# Microcontroller.net
KiCad netlist of a schematic drawn in Altium Designer
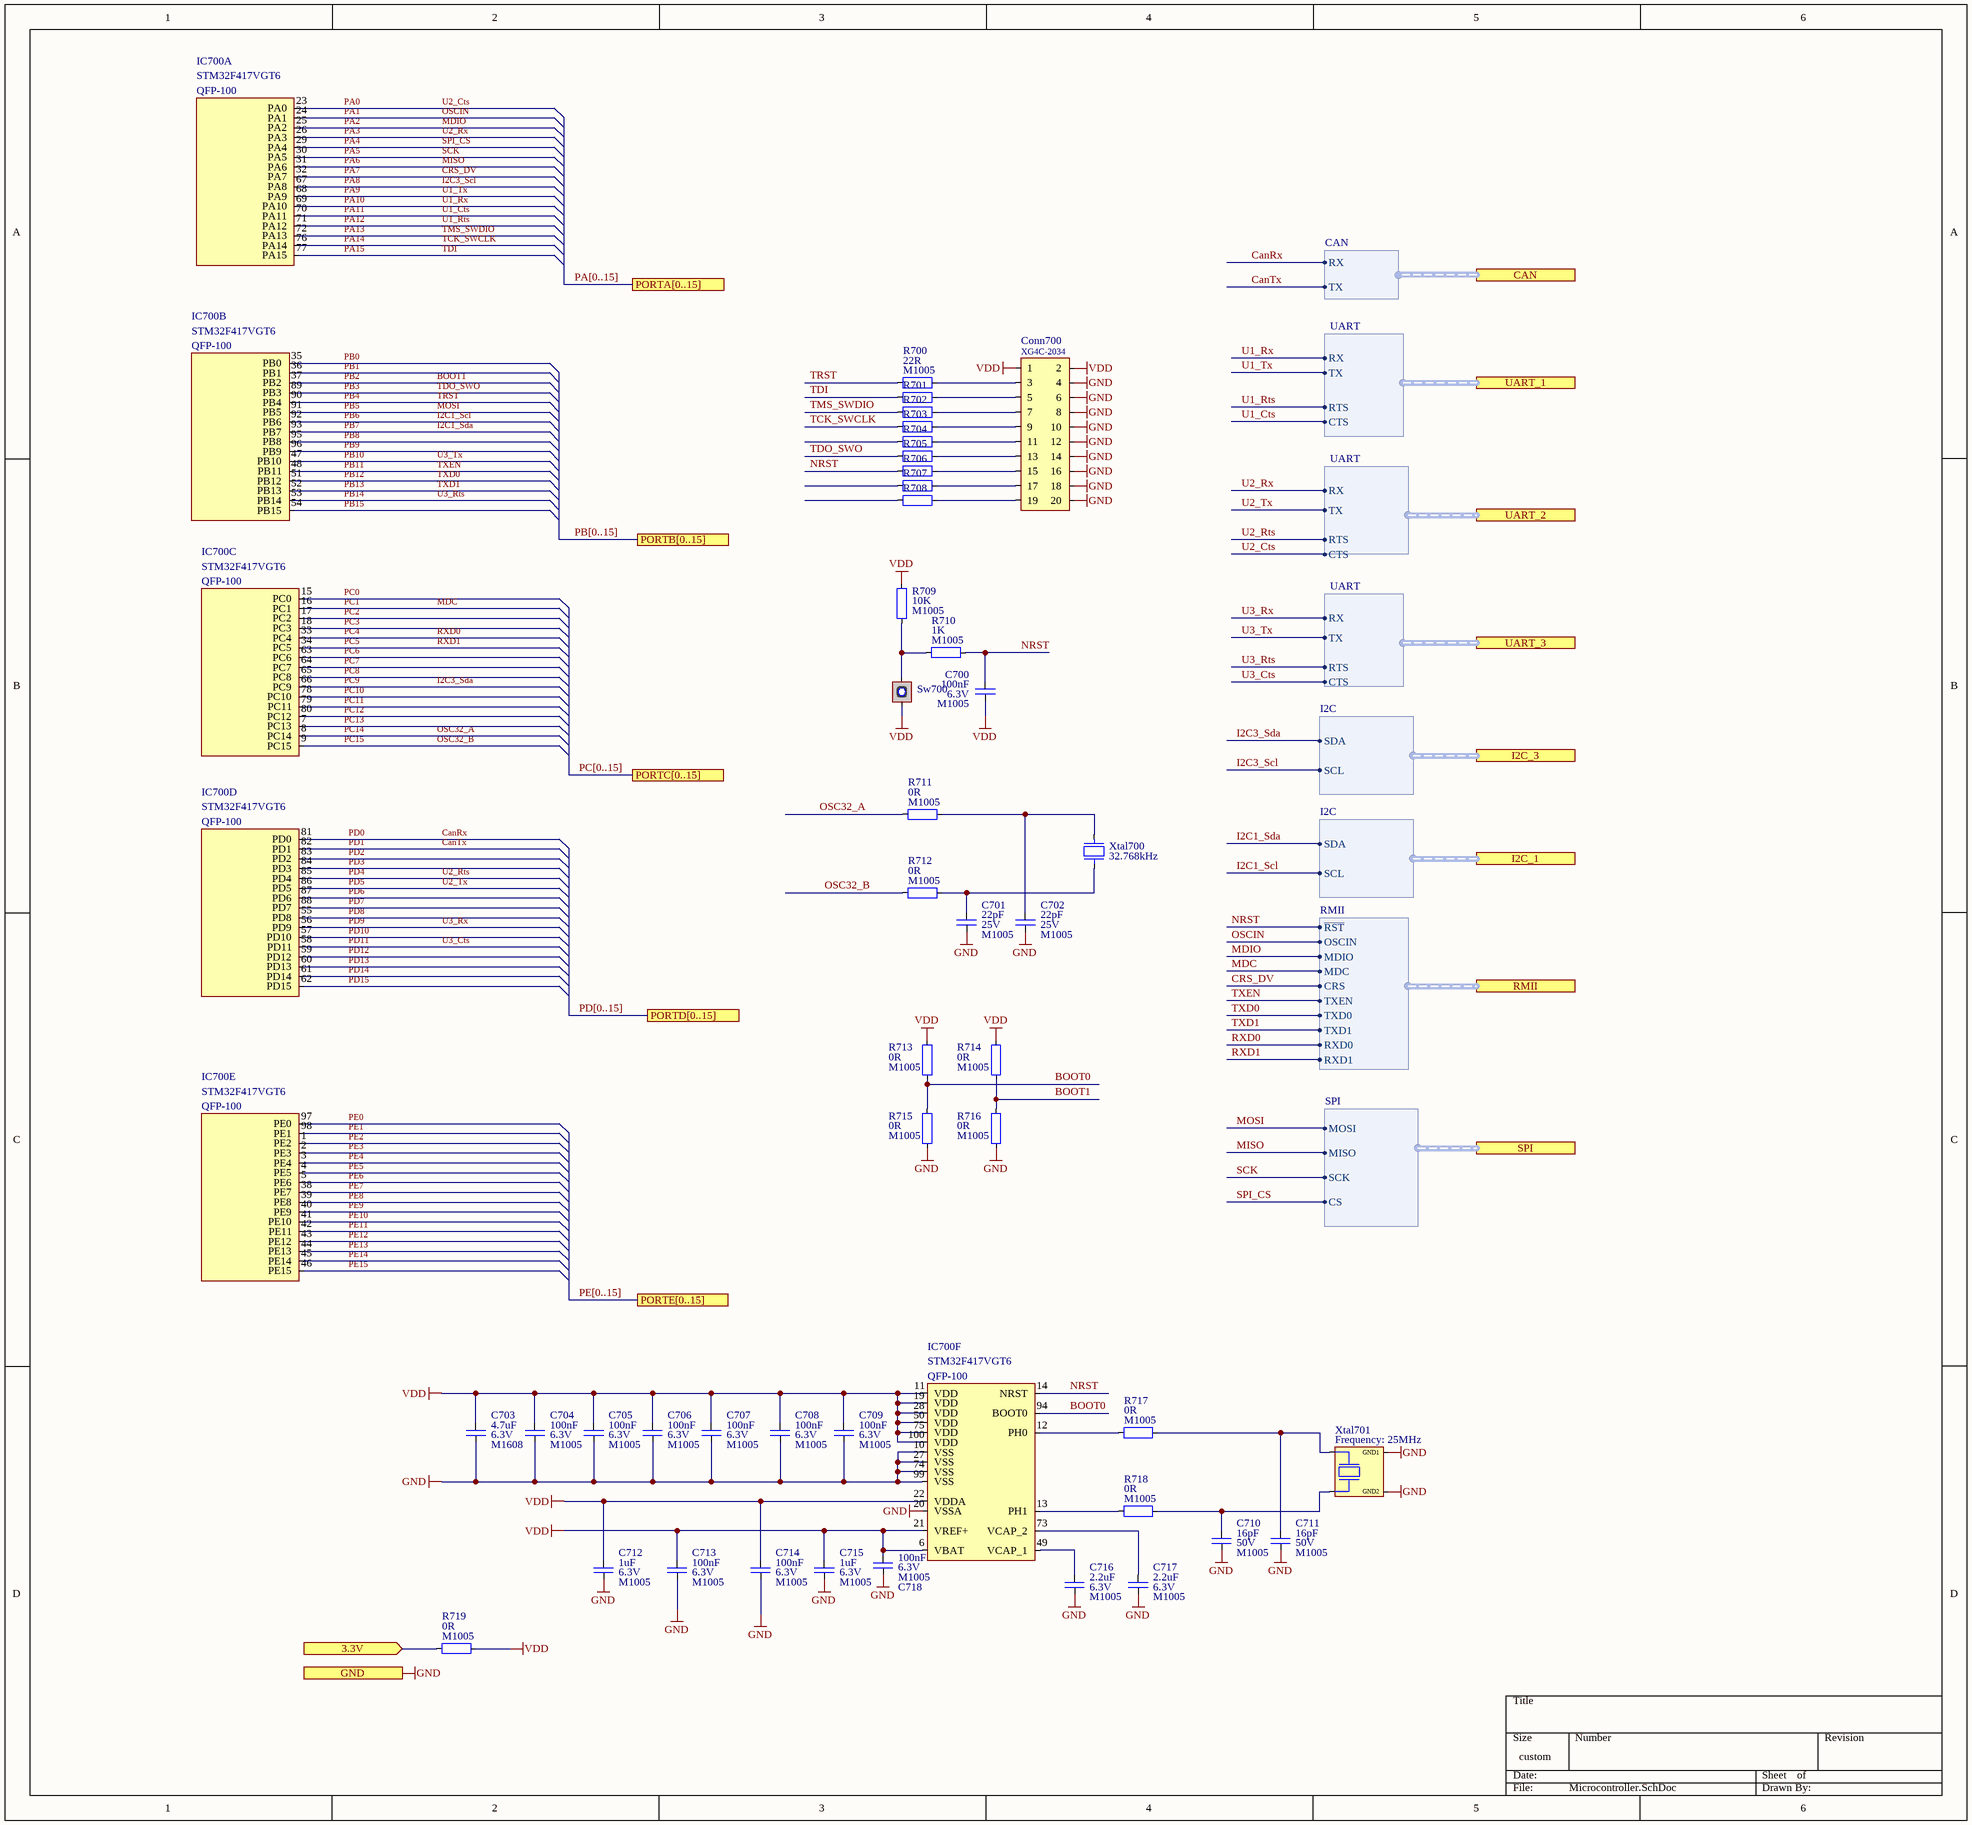
[diagram p0: Microcontroller.SchDoc]

(export (version "E")
  (design (tool "Eeschema 10.0.6"))
  (components
    (comp (ref "C700")
      (value "100nF")
      (footprint "Capacitor_Ceramic_M1005_I0402")
      (description "Cap, Cer, 100nF, 6.3V, M1005")
      (fields
        (field (name "VOLTAGE") "6.3V")
        (field (name "MANUFACTURER PART NUMBER") "04026D104KAT4A")
        (field (name "MANUFACTURER") "Kyocera")
        (field (name "PACKAGE") "M1005")
      )
      (libsource (lib "Capacitor") (part "Capacitor_Ceramic"))
    )
    (comp (ref "C701")
      (value "22pF")
      (footprint "Capacitor_Ceramic_M1005_I0402")
      (description "Cap, Cer, 22pF, 25V, M1005")
      (fields
        (field (name "VOLTAGE") "25V")
        (field (name "MANUFACTURER PART NUMBER") "0402N220J250CT")
        (field (name "MANUFACTURER") "Walsin")
        (field (name "PACKAGE") "M1005")
      )
      (libsource (lib "Capacitor") (part "Capacitor_Ceramic"))
    )
    (comp (ref "C702")
      (value "22pF")
      (footprint "Capacitor_Ceramic_M1005_I0402")
      (description "Cap, Cer, 22pF, 25V, M1005")
      (fields
        (field (name "VOLTAGE") "25V")
        (field (name "MANUFACTURER PART NUMBER") "0402N220J250CT")
        (field (name "MANUFACTURER") "Walsin")
        (field (name "PACKAGE") "M1005")
      )
      (libsource (lib "Capacitor") (part "Capacitor_Ceramic"))
    )
    (comp (ref "C703")
      (value "4.7uF")
      (footprint "Capacitor_Ceramic_M1608_I0603")
      (description "Cap, Cer, 4.7uF, 6.3V, M1608")
      (fields
        (field (name "VOLTAGE") "6.3V")
        (field (name "MANUFACTURER PART NUMBER") "CL10A475KQ8NNNC")
        (field (name "MANUFACTURER") "Samsung")
        (field (name "PACKAGE") "M1608")
      )
      (libsource (lib "Capacitor") (part "Capacitor_Ceramic"))
    )
    (comp (ref "C704")
      (value "100nF")
      (footprint "Capacitor_Ceramic_M1005_I0402")
      (description "Cap, Cer, 100nF, 6.3V, M1005")
      (fields
        (field (name "VOLTAGE") "6.3V")
        (field (name "MANUFACTURER PART NUMBER") "04026D104KAT4A")
        (field (name "MANUFACTURER") "Kyocera")
        (field (name "PACKAGE") "M1005")
      )
      (libsource (lib "Capacitor") (part "Capacitor_Ceramic"))
    )
    (comp (ref "C705")
      (value "100nF")
      (footprint "Capacitor_Ceramic_M1005_I0402")
      (description "Cap, Cer, 100nF, 6.3V, M1005")
      (fields
        (field (name "VOLTAGE") "6.3V")
        (field (name "MANUFACTURER PART NUMBER") "04026D104KAT4A")
        (field (name "MANUFACTURER") "Kyocera")
        (field (name "PACKAGE") "M1005")
      )
      (libsource (lib "Capacitor") (part "Capacitor_Ceramic"))
    )
    (comp (ref "C706")
      (value "100nF")
      (footprint "Capacitor_Ceramic_M1005_I0402")
      (description "Cap, Cer, 100nF, 6.3V, M1005")
      (fields
        (field (name "VOLTAGE") "6.3V")
        (field (name "MANUFACTURER PART NUMBER") "04026D104KAT4A")
        (field (name "MANUFACTURER") "Kyocera")
        (field (name "PACKAGE") "M1005")
      )
      (libsource (lib "Capacitor") (part "Capacitor_Ceramic"))
    )
    (comp (ref "C707")
      (value "100nF")
      (footprint "Capacitor_Ceramic_M1005_I0402")
      (description "Cap, Cer, 100nF, 6.3V, M1005")
      (fields
        (field (name "VOLTAGE") "6.3V")
        (field (name "MANUFACTURER PART NUMBER") "04026D104KAT4A")
        (field (name "MANUFACTURER") "Kyocera")
        (field (name "PACKAGE") "M1005")
      )
      (libsource (lib "Capacitor") (part "Capacitor_Ceramic"))
    )
    (comp (ref "C708")
      (value "100nF")
      (footprint "Capacitor_Ceramic_M1005_I0402")
      (description "Cap, Cer, 100nF, 6.3V, M1005")
      (fields
        (field (name "VOLTAGE") "6.3V")
        (field (name "MANUFACTURER PART NUMBER") "04026D104KAT4A")
        (field (name "MANUFACTURER") "Kyocera")
        (field (name "PACKAGE") "M1005")
      )
      (libsource (lib "Capacitor") (part "Capacitor_Ceramic"))
    )
    (comp (ref "C709")
      (value "100nF")
      (footprint "Capacitor_Ceramic_M1005_I0402")
      (description "Cap, Cer, 100nF, 6.3V, M1005")
      (fields
        (field (name "VOLTAGE") "6.3V")
        (field (name "MANUFACTURER PART NUMBER") "04026D104KAT4A")
        (field (name "MANUFACTURER") "Kyocera")
        (field (name "PACKAGE") "M1005")
      )
      (libsource (lib "Capacitor") (part "Capacitor_Ceramic"))
    )
    (comp (ref "C710")
      (value "16pF")
      (footprint "Capacitor_Ceramic_M1005_I0402")
      (description "Cap, Cer, 16pF, 50V, M1005")
      (fields
        (field (name "VOLTAGE") "50V")
        (field (name "MANUFACTURER PART NUMBER") "0402N160J500CT")
        (field (name "MANUFACTURER") "Walsin")
        (field (name "PACKAGE") "M1005")
      )
      (libsource (lib "Capacitor") (part "Capacitor_Ceramic"))
    )
    (comp (ref "C711")
      (value "16pF")
      (footprint "Capacitor_Ceramic_M1005_I0402")
      (description "Cap, Cer, 16pF, 50V, M1005")
      (fields
        (field (name "VOLTAGE") "50V")
        (field (name "MANUFACTURER PART NUMBER") "0402N160J500CT")
        (field (name "MANUFACTURER") "Walsin")
        (field (name "PACKAGE") "M1005")
      )
      (libsource (lib "Capacitor") (part "Capacitor_Ceramic"))
    )
    (comp (ref "C712")
      (value "1uF")
      (footprint "Capacitor_Ceramic_M1005_I0402")
      (description "Cap, Cer, 1uF, 6.3V, M1005")
      (fields
        (field (name "VOLTAGE") "6.3V")
        (field (name "MANUFACTURER PART NUMBER") "CL05A105MQ5NNNC")
        (field (name "MANUFACTURER") "Samsung")
        (field (name "PACKAGE") "M1005")
      )
      (libsource (lib "Capacitor") (part "Capacitor_Ceramic"))
    )
    (comp (ref "C713")
      (value "100nF")
      (footprint "Capacitor_Ceramic_M1005_I0402")
      (description "Cap, Cer, 100nF, 6.3V, M1005")
      (fields
        (field (name "VOLTAGE") "6.3V")
        (field (name "MANUFACTURER PART NUMBER") "04026D104KAT4A")
        (field (name "MANUFACTURER") "Kyocera")
        (field (name "PACKAGE") "M1005")
      )
      (libsource (lib "Capacitor") (part "Capacitor_Ceramic"))
    )
    (comp (ref "C714")
      (value "100nF")
      (footprint "Capacitor_Ceramic_M1005_I0402")
      (description "Cap, Cer, 100nF, 6.3V, M1005")
      (fields
        (field (name "VOLTAGE") "6.3V")
        (field (name "MANUFACTURER PART NUMBER") "04026D104KAT4A")
        (field (name "MANUFACTURER") "Kyocera")
        (field (name "PACKAGE") "M1005")
      )
      (libsource (lib "Capacitor") (part "Capacitor_Ceramic"))
    )
    (comp (ref "C715")
      (value "1uF")
      (footprint "Capacitor_Ceramic_M1005_I0402")
      (description "Cap, Cer, 1uF, 6.3V, M1005")
      (fields
        (field (name "VOLTAGE") "6.3V")
        (field (name "MANUFACTURER PART NUMBER") "CL05A105MQ5NNNC")
        (field (name "MANUFACTURER") "Samsung")
        (field (name "PACKAGE") "M1005")
      )
      (libsource (lib "Capacitor") (part "Capacitor_Ceramic"))
    )
    (comp (ref "C716")
      (value "2.2uF")
      (footprint "Capacitor_Ceramic_M1005_I0402")
      (description "Cap, Cer, 2.2uF, 6.3V, M1005")
      (fields
        (field (name "VOLTAGE") "6.3V")
        (field (name "MANUFACTURER PART NUMBER") "CL05A225MQ5NNNC")
        (field (name "MANUFACTURER") "Samsung")
        (field (name "PACKAGE") "M1005")
      )
      (libsource (lib "Capacitor") (part "Capacitor_Ceramic"))
    )
    (comp (ref "C717")
      (value "2.2uF")
      (footprint "Capacitor_Ceramic_M1005_I0402")
      (description "Cap, Cer, 2.2uF, 6.3V, M1005")
      (fields
        (field (name "VOLTAGE") "6.3V")
        (field (name "MANUFACTURER PART NUMBER") "CL05A225MQ5NNNC")
        (field (name "MANUFACTURER") "Samsung")
        (field (name "PACKAGE") "M1005")
      )
      (libsource (lib "Capacitor") (part "Capacitor_Ceramic"))
    )
    (comp (ref "C718")
      (value "100nF")
      (footprint "Capacitor_Ceramic_M1005_I0402")
      (description "Cap, Cer, 100nF, 6.3V, M1005")
      (fields
        (field (name "VOLTAGE") "6.3V")
        (field (name "MANUFACTURER PART NUMBER") "04026D104KAT4A")
        (field (name "MANUFACTURER") "Kyocera")
        (field (name "PACKAGE") "M1005")
      )
      (libsource (lib "Capacitor") (part "Capacitor_Ceramic"))
    )
    (comp (ref "Conn700")
      (value "Connector - 20P")
      (footprint "Connector - Omron, XG4C-2034")
      (description "Conn, Header, 20P, RA, TH, Shrouded")
      (fields (field (name "MANUFACTURER") "Omron") (field (name "MANUFACTURER PART NUMBER") "XG4C-2034"))
      (libsource (lib "Connector - Header") (part "Connector - 20P"))
    )
    (comp (ref "IC700")
      (value "STM, STM32F417VxTx")
      (footprint "QFP-100, 14mm x 14mm, 0.5mm")
      (description "IC, MCU, STM32F417, QFP-100")
      (fields
        (field (name "MANUFACTURER") "STM")
        (field (name "MANUFACTURER PART NUMBER") "STM32F417VGT6")
        (field (name "PACKAGE") "QFP-100")
      )
      (libsource (lib "IC - MCU") (part "STM, STM32F417VxTx"))
    )
    (comp (ref "R700")
      (value "22R")
      (footprint "Resistor_Smd_M1005_I0402")
      (description "Res, 22R, 1%, M1005")
      (fields
        (field (name "TOLERANCE") "1%")
        (field (name "MANUFACTURER") "Yageo")
        (field (name "PACKAGE") "M1005")
      )
      (libsource (lib "Resistor") (part "Resistor"))
    )
    (comp (ref "R701")
      (value "Resistor")
      (footprint "Resistor_Smd_M1005_I0402")
      (description "Res, 22R, 1%, M1005")
      (fields (field (name "TOLERANCE") "1%") (field (name "MANUFACTURER") "Yageo"))
      (libsource (lib "Resistor") (part "Resistor"))
    )
    (comp (ref "R702")
      (value "Resistor")
      (footprint "Resistor_Smd_M1005_I0402")
      (description "Res, 22R, 1%, M1005")
      (fields (field (name "TOLERANCE") "1%") (field (name "MANUFACTURER") "Yageo"))
      (libsource (lib "Resistor") (part "Resistor"))
    )
    (comp (ref "R703")
      (value "Resistor")
      (footprint "Resistor_Smd_M1005_I0402")
      (description "Res, 22R, 1%, M1005")
      (fields (field (name "TOLERANCE") "1%") (field (name "MANUFACTURER") "Yageo"))
      (libsource (lib "Resistor") (part "Resistor"))
    )
    (comp (ref "R704")
      (value "Resistor")
      (footprint "Resistor_Smd_M1005_I0402")
      (description "Res, 22R, 1%, M1005")
      (fields (field (name "TOLERANCE") "1%") (field (name "MANUFACTURER") "Yageo"))
      (libsource (lib "Resistor") (part "Resistor"))
    )
    (comp (ref "R705")
      (value "Resistor")
      (footprint "Resistor_Smd_M1005_I0402")
      (description "Res, 22R, 1%, M1005")
      (fields (field (name "TOLERANCE") "1%") (field (name "MANUFACTURER") "Yageo"))
      (libsource (lib "Resistor") (part "Resistor"))
    )
    (comp (ref "R706")
      (value "Resistor")
      (footprint "Resistor_Smd_M1005_I0402")
      (description "Res, 22R, 1%, M1005")
      (fields (field (name "TOLERANCE") "1%") (field (name "MANUFACTURER") "Yageo"))
      (libsource (lib "Resistor") (part "Resistor"))
    )
    (comp (ref "R707")
      (value "Resistor")
      (footprint "Resistor_Smd_M1005_I0402")
      (description "Res, 22R, 1%, M1005")
      (fields (field (name "TOLERANCE") "1%") (field (name "MANUFACTURER") "Yageo"))
      (libsource (lib "Resistor") (part "Resistor"))
    )
    (comp (ref "R708")
      (value "Resistor")
      (footprint "Resistor_Smd_M1005_I0402")
      (description "Res, 22R, 1%, M1005")
      (fields (field (name "TOLERANCE") "1%") (field (name "MANUFACTURER") "Yageo"))
      (libsource (lib "Resistor") (part "Resistor"))
    )
    (comp (ref "R709")
      (value "10K")
      (footprint "Resistor_Smd_M1005_I0402")
      (description "Res, 10K, 1%, M1005")
      (fields
        (field (name "TOLERANCE") "1%")
        (field (name "MANUFACTURER") "Yageo")
        (field (name "PACKAGE") "M1005")
      )
      (libsource (lib "Resistor") (part "Resistor"))
    )
    (comp (ref "R710")
      (value "1K")
      (footprint "Resistor_Smd_M1005_I0402")
      (description "Res, 1K, 1%, M1005")
      (fields
        (field (name "TOLERANCE") "1%")
        (field (name "MANUFACTURER") "Yageo")
        (field (name "PACKAGE") "M1005")
      )
      (libsource (lib "Resistor") (part "Resistor"))
    )
    (comp (ref "R711")
      (value "0R")
      (footprint "Resistor_Smd_M1005_I0402")
      (description "Res, 0R, M1005")
      (fields
        (field (name "MANUFACTURER") "Yageo")
        (field (name "MANUFACTURER PART NUMBER") "RC0402FR-070RL")
        (field (name "PACKAGE") "M1005")
      )
      (libsource (lib "Resistor") (part "Resistor"))
    )
    (comp (ref "R712")
      (value "0R")
      (footprint "Resistor_Smd_M1005_I0402")
      (description "Res, 0R, M1005")
      (fields
        (field (name "MANUFACTURER") "Yageo")
        (field (name "MANUFACTURER PART NUMBER") "RC0402FR-070RL")
        (field (name "PACKAGE") "M1005")
      )
      (libsource (lib "Resistor") (part "Resistor"))
    )
    (comp (ref "R713")
      (value "0R")
      (footprint "Resistor_Smd_M1005_I0402")
      (description "Res, 0R, M1005")
      (fields
        (field (name "MANUFACTURER") "Yageo")
        (field (name "MANUFACTURER PART NUMBER") "RC0402FR-070RL")
        (field (name "PACKAGE") "M1005")
      )
      (libsource (lib "Resistor") (part "Resistor"))
    )
    (comp (ref "R714")
      (value "0R")
      (footprint "Resistor_Smd_M1005_I0402")
      (description "Res, 0R, M1005")
      (fields
        (field (name "MANUFACTURER") "Yageo")
        (field (name "MANUFACTURER PART NUMBER") "RC0402FR-070RL")
        (field (name "PACKAGE") "M1005")
      )
      (libsource (lib "Resistor") (part "Resistor"))
    )
    (comp (ref "R715")
      (value "0R")
      (footprint "Resistor_Smd_M1005_I0402")
      (description "Res, 0R, M1005")
      (fields
        (field (name "MANUFACTURER") "Yageo")
        (field (name "MANUFACTURER PART NUMBER") "RC0402FR-070RL")
        (field (name "PACKAGE") "M1005")
      )
      (libsource (lib "Resistor") (part "Resistor"))
    )
    (comp (ref "R716")
      (value "0R")
      (footprint "Resistor_Smd_M1005_I0402")
      (description "Res, 0R, M1005")
      (fields
        (field (name "MANUFACTURER") "Yageo")
        (field (name "MANUFACTURER PART NUMBER") "RC0402FR-070RL")
        (field (name "PACKAGE") "M1005")
      )
      (libsource (lib "Resistor") (part "Resistor"))
    )
    (comp (ref "R717")
      (value "0R")
      (footprint "Resistor_Smd_M1005_I0402")
      (description "Res, 0R, M1005")
      (fields
        (field (name "MANUFACTURER") "Yageo")
        (field (name "MANUFACTURER PART NUMBER") "RC0402FR-070RL")
        (field (name "PACKAGE") "M1005")
      )
      (libsource (lib "Resistor") (part "Resistor"))
    )
    (comp (ref "R718")
      (value "0R")
      (footprint "Resistor_Smd_M1005_I0402")
      (description "Res, 0R, M1005")
      (fields
        (field (name "MANUFACTURER") "Yageo")
        (field (name "MANUFACTURER PART NUMBER") "RC0402FR-070RL")
        (field (name "PACKAGE") "M1005")
      )
      (libsource (lib "Resistor") (part "Resistor"))
    )
    (comp (ref "R719")
      (value "0R")
      (footprint "Resistor_Smd_M1005_I0402")
      (description "Res, 0R, M1005")
      (fields
        (field (name "MANUFACTURER") "Yageo")
        (field (name "MANUFACTURER PART NUMBER") "RC0402FR-070RL")
        (field (name "PACKAGE") "M1005")
      )
      (libsource (lib "Resistor") (part "Resistor"))
    )
    (comp (ref "Sw700")
      (value "Tactile, SPST")
      (footprint "Tactile, SPST - Panasonic, EVQQ2")
      (libsource (lib "Switch") (part "Tactile, SPST"))
    )
    (comp (ref "Xtal700")
      (value "Crystal")
      (footprint "NDK, NX3215SA")
      (description "XTAL, 32.768kHz, 12.5pF")
      (fields
        (field (name "MANUFACTURER") "NDK")
        (field (name "FREQUENCY") "32.768kHz")
        (field (name "MANUFACTURER PART NUMBER") "NX3215SA-32.768K-STD-MUS-2")
      )
      (libsource (lib "Crystal") (part "Crystal"))
    )
    (comp (ref "Xtal701")
      (value "Crystal, Two Gnd Pins")
      (footprint "Kyocera, CX3225SB")
      (description "XTAL, 25MHz, 12pF")
      (fields
        (field (name "MANUFACTURER") "Kyocera")
        (field (name "FREQUENCY") "25MHz")
        (field (name "MANUFACTURER PART NUMBER") "CX3225SB25000H0FLJCC")
      )
      (libsource (lib "Crystal") (part "Crystal, Two Gnd Pins"))
    )
  )
  (nets
    (net (code "6") (name "/3.3V") (class "Default")
      (node (ref "R719") (pin "1") (pinfunction "1_1") (pintype "passive"))
    )
    (net (code "7") (name "/BOOT0") (class "Default")
      (node (ref "IC700") (pin "94") (pinfunction "BOOT0_94") (pintype "passive"))
      (node (ref "R713") (pin "1") (pinfunction "1_1") (pintype "passive"))
      (node (ref "R715") (pin "2") (pinfunction "2_2") (pintype "passive"))
    )
    (net (code "8") (name "/NRST") (class "Default")
      (node (ref "C700") (pin "1") (pinfunction "1_1") (pintype "passive"))
      (node (ref "IC700") (pin "14") (pinfunction "NRST_14") (pintype "passive"))
      (node (ref "R706") (pin "1") (pinfunction "1_1") (pintype "passive"))
      (node (ref "R710") (pin "2") (pinfunction "2_2") (pintype "passive"))
    )
    (net (code "9") (name "/PA0") (class "Default")
      (node (ref "IC700") (pin "23") (pinfunction "PA0_23") (pintype "passive"))
    )
    (net (code "10") (name "/PA1") (class "Default")
      (node (ref "IC700") (pin "24") (pinfunction "PA1_24") (pintype "passive"))
    )
    (net (code "11") (name "/PA2") (class "Default")
      (node (ref "IC700") (pin "25") (pinfunction "PA2_25") (pintype "passive"))
    )
    (net (code "12") (name "/PA3") (class "Default")
      (node (ref "IC700") (pin "26") (pinfunction "PA3_26") (pintype "passive"))
    )
    (net (code "13") (name "/PA4") (class "Default")
      (node (ref "IC700") (pin "29") (pinfunction "PA4_29") (pintype "passive"))
    )
    (net (code "14") (name "/PA5") (class "Default")
      (node (ref "IC700") (pin "30") (pinfunction "PA5_30") (pintype "passive"))
    )
    (net (code "15") (name "/PA6") (class "Default")
      (node (ref "IC700") (pin "31") (pinfunction "PA6_31") (pintype "passive"))
    )
    (net (code "16") (name "/PA7") (class "Default")
      (node (ref "IC700") (pin "32") (pinfunction "PA7_32") (pintype "passive"))
    )
    (net (code "17") (name "/PA8") (class "Default")
      (node (ref "IC700") (pin "67") (pinfunction "PA8_67") (pintype "passive"))
    )
    (net (code "18") (name "/PA9") (class "Default")
      (node (ref "IC700") (pin "68") (pinfunction "PA9_68") (pintype "passive"))
    )
    (net (code "19") (name "/PA10") (class "Default")
      (node (ref "IC700") (pin "69") (pinfunction "PA10_69") (pintype "passive"))
    )
    (net (code "20") (name "/PA11") (class "Default")
      (node (ref "IC700") (pin "70") (pinfunction "PA11_70") (pintype "passive"))
    )
    (net (code "21") (name "/PA12") (class "Default")
      (node (ref "IC700") (pin "71") (pinfunction "PA12_71") (pintype "passive"))
    )
    (net (code "22") (name "/PA13") (class "Default")
      (node (ref "IC700") (pin "72") (pinfunction "PA13_72") (pintype "passive"))
      (node (ref "R702") (pin "1") (pinfunction "1_1") (pintype "passive"))
    )
    (net (code "23") (name "/PA14") (class "Default")
      (node (ref "IC700") (pin "76") (pinfunction "PA14_76") (pintype "passive"))
      (node (ref "R703") (pin "1") (pinfunction "1_1") (pintype "passive"))
    )
    (net (code "24") (name "/PA15") (class "Default")
      (node (ref "IC700") (pin "77") (pinfunction "PA15_77") (pintype "passive"))
      (node (ref "R701") (pin "1") (pinfunction "1_1") (pintype "passive"))
    )
    (net (code "26") (name "/PB0") (class "Default")
      (node (ref "IC700") (pin "35") (pinfunction "PB0_35") (pintype "passive"))
    )
    (net (code "27") (name "/PB1") (class "Default")
      (node (ref "IC700") (pin "36") (pinfunction "PB1_36") (pintype "passive"))
    )
    (net (code "28") (name "/PB2") (class "Default")
      (node (ref "IC700") (pin "37") (pinfunction "PB2_37") (pintype "passive"))
      (node (ref "R714") (pin "1") (pinfunction "1_1") (pintype "passive"))
      (node (ref "R716") (pin "2") (pinfunction "2_2") (pintype "passive"))
    )
    (net (code "29") (name "/PB3") (class "Default")
      (node (ref "IC700") (pin "89") (pinfunction "PB3_89") (pintype "passive"))
      (node (ref "R705") (pin "1") (pinfunction "1_1") (pintype "passive"))
    )
    (net (code "30") (name "/PB4") (class "Default")
      (node (ref "IC700") (pin "90") (pinfunction "PB4_90") (pintype "passive"))
      (node (ref "R700") (pin "1") (pinfunction "1_1") (pintype "passive"))
    )
    (net (code "31") (name "/PB5") (class "Default")
      (node (ref "IC700") (pin "91") (pinfunction "PB5_91") (pintype "passive"))
    )
    (net (code "32") (name "/PB6") (class "Default")
      (node (ref "IC700") (pin "92") (pinfunction "PB6_92") (pintype "passive"))
    )
    (net (code "33") (name "/PB7") (class "Default")
      (node (ref "IC700") (pin "93") (pinfunction "PB7_93") (pintype "passive"))
    )
    (net (code "34") (name "/PB8") (class "Default")
      (node (ref "IC700") (pin "95") (pinfunction "PB8_95") (pintype "passive"))
    )
    (net (code "35") (name "/PB9") (class "Default")
      (node (ref "IC700") (pin "96") (pinfunction "PB9_96") (pintype "passive"))
    )
    (net (code "36") (name "/PB10") (class "Default")
      (node (ref "IC700") (pin "47") (pinfunction "PB10_47") (pintype "passive"))
    )
    (net (code "37") (name "/PB11") (class "Default")
      (node (ref "IC700") (pin "48") (pinfunction "PB11_48") (pintype "passive"))
    )
    (net (code "38") (name "/PB12") (class "Default")
      (node (ref "IC700") (pin "51") (pinfunction "PB12_51") (pintype "passive"))
    )
    (net (code "39") (name "/PB13") (class "Default")
      (node (ref "IC700") (pin "52") (pinfunction "PB13_52") (pintype "passive"))
    )
    (net (code "40") (name "/PB14") (class "Default")
      (node (ref "IC700") (pin "53") (pinfunction "PB14_53") (pintype "passive"))
    )
    (net (code "41") (name "/PB15") (class "Default")
      (node (ref "IC700") (pin "54") (pinfunction "PB15_54") (pintype "passive"))
    )
    (net (code "43") (name "/PC0") (class "Default")
      (node (ref "IC700") (pin "15") (pinfunction "PC0_15") (pintype "passive"))
    )
    (net (code "44") (name "/PC1") (class "Default")
      (node (ref "IC700") (pin "16") (pinfunction "PC1_16") (pintype "passive"))
    )
    (net (code "45") (name "/PC2") (class "Default")
      (node (ref "IC700") (pin "17") (pinfunction "PC2_17") (pintype "passive"))
    )
    (net (code "46") (name "/PC3") (class "Default")
      (node (ref "IC700") (pin "18") (pinfunction "PC3_18") (pintype "passive"))
    )
    (net (code "47") (name "/PC4") (class "Default")
      (node (ref "IC700") (pin "33") (pinfunction "PC4_33") (pintype "passive"))
    )
    (net (code "48") (name "/PC5") (class "Default")
      (node (ref "IC700") (pin "34") (pinfunction "PC5_34") (pintype "passive"))
    )
    (net (code "49") (name "/PC6") (class "Default")
      (node (ref "IC700") (pin "63") (pinfunction "PC6_63") (pintype "passive"))
    )
    (net (code "50") (name "/PC7") (class "Default")
      (node (ref "IC700") (pin "64") (pinfunction "PC7_64") (pintype "passive"))
    )
    (net (code "51") (name "/PC8") (class "Default")
      (node (ref "IC700") (pin "65") (pinfunction "PC8_65") (pintype "passive"))
    )
    (net (code "52") (name "/PC9") (class "Default")
      (node (ref "IC700") (pin "66") (pinfunction "PC9_66") (pintype "passive"))
    )
    (net (code "53") (name "/PC10") (class "Default")
      (node (ref "IC700") (pin "78") (pinfunction "PC10_78") (pintype "passive"))
    )
    (net (code "54") (name "/PC11") (class "Default")
      (node (ref "IC700") (pin "79") (pinfunction "PC11_79") (pintype "passive"))
    )
    (net (code "55") (name "/PC12") (class "Default")
      (node (ref "IC700") (pin "80") (pinfunction "PC12_80") (pintype "passive"))
    )
    (net (code "56") (name "/PC13") (class "Default")
      (node (ref "IC700") (pin "7") (pinfunction "PC13_7") (pintype "passive"))
    )
    (net (code "57") (name "/PC14") (class "Default")
      (node (ref "IC700") (pin "8") (pinfunction "PC14_8") (pintype "passive"))
      (node (ref "R711") (pin "1") (pinfunction "1_1") (pintype "passive"))
    )
    (net (code "58") (name "/PC15") (class "Default")
      (node (ref "IC700") (pin "9") (pinfunction "PC15_9") (pintype "passive"))
      (node (ref "R712") (pin "1") (pinfunction "1_1") (pintype "passive"))
    )
    (net (code "60") (name "/PD0") (class "Default")
      (node (ref "IC700") (pin "81") (pinfunction "PD0_81") (pintype "passive"))
    )
    (net (code "61") (name "/PD1") (class "Default")
      (node (ref "IC700") (pin "82") (pinfunction "PD1_82") (pintype "passive"))
    )
    (net (code "62") (name "/PD2") (class "Default")
      (node (ref "IC700") (pin "83") (pinfunction "PD2_83") (pintype "passive"))
    )
    (net (code "63") (name "/PD3") (class "Default")
      (node (ref "IC700") (pin "84") (pinfunction "PD3_84") (pintype "passive"))
    )
    (net (code "64") (name "/PD4") (class "Default")
      (node (ref "IC700") (pin "85") (pinfunction "PD4_85") (pintype "passive"))
    )
    (net (code "65") (name "/PD5") (class "Default")
      (node (ref "IC700") (pin "86") (pinfunction "PD5_86") (pintype "passive"))
    )
    (net (code "66") (name "/PD6") (class "Default")
      (node (ref "IC700") (pin "87") (pinfunction "PD6_87") (pintype "passive"))
    )
    (net (code "67") (name "/PD7") (class "Default")
      (node (ref "IC700") (pin "88") (pinfunction "PD7_88") (pintype "passive"))
    )
    (net (code "68") (name "/PD8") (class "Default")
      (node (ref "IC700") (pin "55") (pinfunction "PD8_55") (pintype "passive"))
    )
    (net (code "69") (name "/PD9") (class "Default")
      (node (ref "IC700") (pin "56") (pinfunction "PD9_56") (pintype "passive"))
    )
    (net (code "70") (name "/PD10") (class "Default")
      (node (ref "IC700") (pin "57") (pinfunction "PD10_57") (pintype "passive"))
    )
    (net (code "71") (name "/PD11") (class "Default")
      (node (ref "IC700") (pin "58") (pinfunction "PD11_58") (pintype "passive"))
    )
    (net (code "72") (name "/PD12") (class "Default")
      (node (ref "IC700") (pin "59") (pinfunction "PD12_59") (pintype "passive"))
    )
    (net (code "73") (name "/PD13") (class "Default")
      (node (ref "IC700") (pin "60") (pinfunction "PD13_60") (pintype "passive"))
    )
    (net (code "74") (name "/PD14") (class "Default")
      (node (ref "IC700") (pin "61") (pinfunction "PD14_61") (pintype "passive"))
    )
    (net (code "75") (name "/PD15") (class "Default")
      (node (ref "IC700") (pin "62") (pinfunction "PD15_62") (pintype "passive"))
    )
    (net (code "77") (name "/PE0") (class "Default")
      (node (ref "IC700") (pin "97") (pinfunction "PE0_97") (pintype "passive"))
    )
    (net (code "78") (name "/PE1") (class "Default")
      (node (ref "IC700") (pin "98") (pinfunction "PE1_98") (pintype "passive"))
    )
    (net (code "79") (name "/PE2") (class "Default")
      (node (ref "IC700") (pin "1") (pinfunction "PE2_1") (pintype "passive"))
    )
    (net (code "80") (name "/PE3") (class "Default")
      (node (ref "IC700") (pin "2") (pinfunction "PE3_2") (pintype "passive"))
    )
    (net (code "81") (name "/PE4") (class "Default")
      (node (ref "IC700") (pin "3") (pinfunction "PE4_3") (pintype "passive"))
    )
    (net (code "82") (name "/PE5") (class "Default")
      (node (ref "IC700") (pin "4") (pinfunction "PE5_4") (pintype "passive"))
    )
    (net (code "83") (name "/PE6") (class "Default")
      (node (ref "IC700") (pin "5") (pinfunction "PE6_5") (pintype "passive"))
    )
    (net (code "84") (name "/PE7") (class "Default")
      (node (ref "IC700") (pin "38") (pinfunction "PE7_38") (pintype "passive"))
    )
    (net (code "85") (name "/PE8") (class "Default")
      (node (ref "IC700") (pin "39") (pinfunction "PE8_39") (pintype "passive"))
    )
    (net (code "86") (name "/PE9") (class "Default")
      (node (ref "IC700") (pin "40") (pinfunction "PE9_40") (pintype "passive"))
    )
    (net (code "87") (name "/PE10") (class "Default")
      (node (ref "IC700") (pin "41") (pinfunction "PE10_41") (pintype "passive"))
    )
    (net (code "88") (name "/PE11") (class "Default")
      (node (ref "IC700") (pin "42") (pinfunction "PE11_42") (pintype "passive"))
    )
    (net (code "89") (name "/PE12") (class "Default")
      (node (ref "IC700") (pin "43") (pinfunction "PE12_43") (pintype "passive"))
    )
    (net (code "90") (name "/PE13") (class "Default")
      (node (ref "IC700") (pin "44") (pinfunction "PE13_44") (pintype "passive"))
    )
    (net (code "91") (name "/PE14") (class "Default")
      (node (ref "IC700") (pin "45") (pinfunction "PE14_45") (pintype "passive"))
    )
    (net (code "92") (name "/PE15") (class "Default")
      (node (ref "IC700") (pin "46") (pinfunction "PE15_46") (pintype "passive"))
    )
    (net (code "99") (name "GND") (class "Default")
      (node (ref "C701") (pin "2") (pinfunction "2_2") (pintype "passive"))
      (node (ref "C702") (pin "2") (pinfunction "2_2") (pintype "passive"))
      (node (ref "C703") (pin "2") (pinfunction "2_2") (pintype "passive"))
      (node (ref "C704") (pin "2") (pinfunction "2_2") (pintype "passive"))
      (node (ref "C705") (pin "2") (pinfunction "2_2") (pintype "passive"))
      (node (ref "C706") (pin "2") (pinfunction "2_2") (pintype "passive"))
      (node (ref "C707") (pin "2") (pinfunction "2_2") (pintype "passive"))
      (node (ref "C708") (pin "2") (pinfunction "2_2") (pintype "passive"))
      (node (ref "C709") (pin "2") (pinfunction "2_2") (pintype "passive"))
      (node (ref "C710") (pin "2") (pinfunction "2_2") (pintype "passive"))
      (node (ref "C711") (pin "2") (pinfunction "2_2") (pintype "passive"))
      (node (ref "C712") (pin "2") (pinfunction "2_2") (pintype "passive"))
      (node (ref "C713") (pin "2") (pinfunction "2_2") (pintype "passive"))
      (node (ref "C714") (pin "2") (pinfunction "2_2") (pintype "passive"))
      (node (ref "C715") (pin "2") (pinfunction "2_2") (pintype "passive"))
      (node (ref "C716") (pin "2") (pinfunction "2_2") (pintype "passive"))
      (node (ref "C717") (pin "2") (pinfunction "2_2") (pintype "passive"))
      (node (ref "C718") (pin "2") (pinfunction "2_2") (pintype "passive"))
      (node (ref "Conn700") (pin "10") (pinfunction "10_10") (pintype "passive"))
      (node (ref "Conn700") (pin "12") (pinfunction "12_12") (pintype "passive"))
      (node (ref "Conn700") (pin "14") (pinfunction "14_14") (pintype "passive"))
      (node (ref "Conn700") (pin "16") (pinfunction "16_16") (pintype "passive"))
      (node (ref "Conn700") (pin "18") (pinfunction "18_18") (pintype "passive"))
      (node (ref "Conn700") (pin "20") (pinfunction "20_20") (pintype "passive"))
      (node (ref "Conn700") (pin "4") (pinfunction "4_4") (pintype "passive"))
      (node (ref "Conn700") (pin "6") (pinfunction "6_6") (pintype "passive"))
      (node (ref "Conn700") (pin "8") (pinfunction "8_8") (pintype "passive"))
      (node (ref "IC700") (pin "10") (pinfunction "VSS_10") (pintype "passive"))
      (node (ref "IC700") (pin "20") (pinfunction "VSSA_20") (pintype "passive"))
      (node (ref "IC700") (pin "27") (pinfunction "VSS_27") (pintype "passive"))
      (node (ref "IC700") (pin "74") (pinfunction "VSS_74") (pintype "passive"))
      (node (ref "IC700") (pin "99") (pinfunction "VSS_99") (pintype "passive"))
      (node (ref "R715") (pin "1") (pinfunction "1_1") (pintype "passive"))
      (node (ref "R716") (pin "1") (pinfunction "1_1") (pintype "passive"))
      (node (ref "Xtal701") (pin "GND1") (pinfunction "GND1_GND1") (pintype "passive"))
      (node (ref "Xtal701") (pin "GND2") (pinfunction "GND2_GND2") (pintype "passive"))
    )
    (net (code "100") (name "Net-(C701-Pad1)") (class "Default")
      (node (ref "C701") (pin "1") (pinfunction "1_1") (pintype "passive"))
      (node (ref "R712") (pin "2") (pinfunction "2_2") (pintype "passive"))
      (node (ref "Xtal700") (pin "2") (pinfunction "2_2") (pintype "passive"))
    )
    (net (code "101") (name "Net-(C702-Pad1)") (class "Default")
      (node (ref "C702") (pin "1") (pinfunction "1_1") (pintype "passive"))
      (node (ref "R711") (pin "2") (pinfunction "2_2") (pintype "passive"))
      (node (ref "Xtal700") (pin "1") (pinfunction "1_1") (pintype "passive"))
    )
    (net (code "102") (name "Net-(C710-Pad1)") (class "Default")
      (node (ref "C710") (pin "1") (pinfunction "1_1") (pintype "passive"))
      (node (ref "R718") (pin "2") (pinfunction "2_2") (pintype "passive"))
      (node (ref "Xtal701") (pin "1") (pinfunction "1_1") (pintype "passive"))
    )
    (net (code "103") (name "Net-(C711-Pad1)") (class "Default")
      (node (ref "C711") (pin "1") (pinfunction "1_1") (pintype "passive"))
      (node (ref "R717") (pin "2") (pinfunction "2_2") (pintype "passive"))
      (node (ref "Xtal701") (pin "2") (pinfunction "2_2") (pintype "passive"))
    )
    (net (code "104") (name "Net-(Conn700-Pad3)") (class "Default")
      (node (ref "Conn700") (pin "3") (pinfunction "3_3") (pintype "passive"))
      (node (ref "R700") (pin "2") (pinfunction "2_2") (pintype "passive"))
    )
    (net (code "105") (name "Net-(Conn700-Pad5)") (class "Default")
      (node (ref "Conn700") (pin "5") (pinfunction "5_5") (pintype "passive"))
      (node (ref "R701") (pin "2") (pinfunction "2_2") (pintype "passive"))
    )
    (net (code "106") (name "Net-(Conn700-Pad7)") (class "Default")
      (node (ref "Conn700") (pin "7") (pinfunction "7_7") (pintype "passive"))
      (node (ref "R702") (pin "2") (pinfunction "2_2") (pintype "passive"))
    )
    (net (code "107") (name "Net-(Conn700-Pad9)") (class "Default")
      (node (ref "Conn700") (pin "9") (pinfunction "9_9") (pintype "passive"))
      (node (ref "R703") (pin "2") (pinfunction "2_2") (pintype "passive"))
    )
    (net (code "108") (name "Net-(Conn700-Pad11)") (class "Default")
      (node (ref "Conn700") (pin "11") (pinfunction "11_11") (pintype "passive"))
      (node (ref "R704") (pin "2") (pinfunction "2_2") (pintype "passive"))
    )
    (net (code "109") (name "Net-(Conn700-Pad13)") (class "Default")
      (node (ref "Conn700") (pin "13") (pinfunction "13_13") (pintype "passive"))
      (node (ref "R705") (pin "2") (pinfunction "2_2") (pintype "passive"))
    )
    (net (code "110") (name "Net-(Conn700-Pad15)") (class "Default")
      (node (ref "Conn700") (pin "15") (pinfunction "15_15") (pintype "passive"))
      (node (ref "R706") (pin "2") (pinfunction "2_2") (pintype "passive"))
    )
    (net (code "111") (name "Net-(Conn700-Pad17)") (class "Default")
      (node (ref "Conn700") (pin "17") (pinfunction "17_17") (pintype "passive"))
      (node (ref "R707") (pin "2") (pinfunction "2_2") (pintype "passive"))
    )
    (net (code "112") (name "Net-(Conn700-Pad19)") (class "Default")
      (node (ref "Conn700") (pin "19") (pinfunction "19_19") (pintype "passive"))
      (node (ref "R708") (pin "2") (pinfunction "2_2") (pintype "passive"))
    )
    (net (code "113") (name "Net-(IC700F-PH0)") (class "Default")
      (node (ref "IC700") (pin "12") (pinfunction "PH0_12") (pintype "passive"))
      (node (ref "R717") (pin "1") (pinfunction "1_1") (pintype "passive"))
    )
    (net (code "114") (name "Net-(IC700F-PH1)") (class "Default")
      (node (ref "IC700") (pin "13") (pinfunction "PH1_13") (pintype "passive"))
      (node (ref "R718") (pin "1") (pinfunction "1_1") (pintype "passive"))
    )
    (net (code "115") (name "Net-(IC700F-VCAP_1)") (class "Default")
      (node (ref "C716") (pin "1") (pinfunction "1_1") (pintype "passive"))
      (node (ref "IC700") (pin "49") (pinfunction "VCAP_1_49") (pintype "passive"))
    )
    (net (code "116") (name "Net-(IC700F-VCAP_2)") (class "Default")
      (node (ref "C717") (pin "1") (pinfunction "1_1") (pintype "passive"))
      (node (ref "IC700") (pin "73") (pinfunction "VCAP_2_73") (pintype "passive"))
    )
    (net (code "117") (name "Net-(R709-Pad2)") (class "Default")
      (node (ref "R709") (pin "2") (pinfunction "2_2") (pintype "passive"))
      (node (ref "R710") (pin "1") (pinfunction "1_1") (pintype "passive"))
      (node (ref "Sw700") (pin "A") (pinfunction "A_A") (pintype "passive"))
    )
    (net (code "118") (name "VDD") (class "Default")
      (node (ref "C700") (pin "2") (pinfunction "2_2") (pintype "passive"))
      (node (ref "C703") (pin "1") (pinfunction "1_1") (pintype "passive"))
      (node (ref "C704") (pin "1") (pinfunction "1_1") (pintype "passive"))
      (node (ref "C705") (pin "1") (pinfunction "1_1") (pintype "passive"))
      (node (ref "C706") (pin "1") (pinfunction "1_1") (pintype "passive"))
      (node (ref "C707") (pin "1") (pinfunction "1_1") (pintype "passive"))
      (node (ref "C708") (pin "1") (pinfunction "1_1") (pintype "passive"))
      (node (ref "C709") (pin "1") (pinfunction "1_1") (pintype "passive"))
      (node (ref "C712") (pin "1") (pinfunction "1_1") (pintype "passive"))
      (node (ref "C713") (pin "1") (pinfunction "1_1") (pintype "passive"))
      (node (ref "C714") (pin "1") (pinfunction "1_1") (pintype "passive"))
      (node (ref "C715") (pin "1") (pinfunction "1_1") (pintype "passive"))
      (node (ref "C718") (pin "1") (pinfunction "1_1") (pintype "passive"))
      (node (ref "Conn700") (pin "1") (pinfunction "1_1") (pintype "passive"))
      (node (ref "Conn700") (pin "2") (pinfunction "2_2") (pintype "passive"))
      (node (ref "IC700") (pin "100") (pinfunction "VDD_100") (pintype "passive"))
      (node (ref "IC700") (pin "11") (pinfunction "VDD_11") (pintype "passive"))
      (node (ref "IC700") (pin "19") (pinfunction "VDD_19") (pintype "passive"))
      (node (ref "IC700") (pin "21") (pinfunction "VREF+_21") (pintype "passive"))
      (node (ref "IC700") (pin "22") (pinfunction "VDDA_22") (pintype "passive"))
      (node (ref "IC700") (pin "28") (pinfunction "VDD_28") (pintype "passive"))
      (node (ref "IC700") (pin "50") (pinfunction "VDD_50") (pintype "passive"))
      (node (ref "IC700") (pin "6") (pinfunction "VBAT_6") (pintype "passive"))
      (node (ref "IC700") (pin "75") (pinfunction "VDD_75") (pintype "passive"))
      (node (ref "R709") (pin "1") (pinfunction "1_1") (pintype "passive"))
      (node (ref "R713") (pin "2") (pinfunction "2_2") (pintype "passive"))
      (node (ref "R714") (pin "2") (pinfunction "2_2") (pintype "passive"))
      (node (ref "R719") (pin "2") (pinfunction "2_2") (pintype "passive"))
      (node (ref "Sw700") (pin "B") (pinfunction "B_B") (pintype "passive"))
    )
    (net (code "119") (name "unconnected-(R704-Pad1)") (class "Default")
      (node (ref "R704") (pin "1") (pinfunction "1_1") (pintype "passive"))
    )
    (net (code "120") (name "unconnected-(R707-Pad1)") (class "Default")
      (node (ref "R707") (pin "1") (pinfunction "1_1") (pintype "passive"))
    )
    (net (code "121") (name "unconnected-(R708-Pad1)") (class "Default")
      (node (ref "R708") (pin "1") (pinfunction "1_1") (pintype "passive"))
    )
  )
)
